# TALLER2.net
KiCad netlist of a schematic drawn in EAGLE
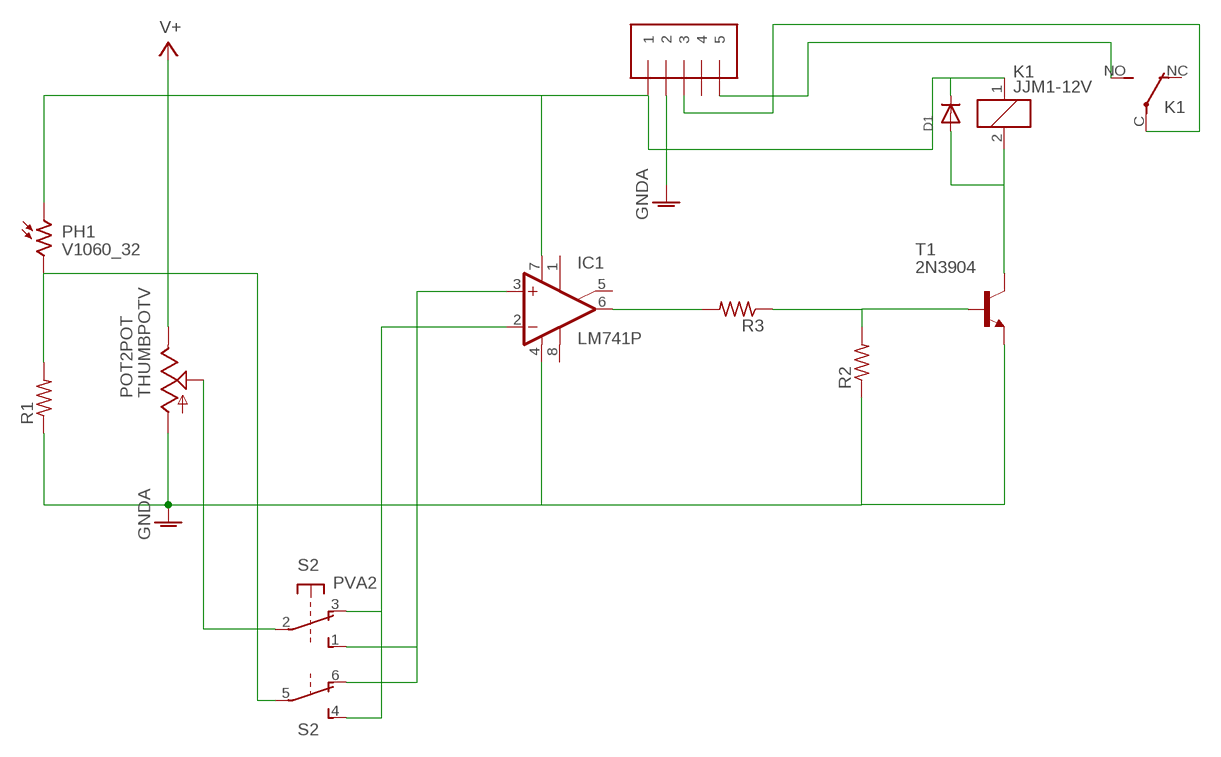
[diagram p0: schematic, sheet 1]

(export (version "E")
  (design (tool "Eeschema 10.0.6"))
  (components
    (comp (ref "D1")
      (value "DIODEDO-1N4148")
      (footprint "eagle-import:DO-1N4148")
      (libsource (lib "eagle-import") (part "DIODEDO-1N4148"))
    )
    (comp (ref "IC1")
      (value "LM741P")
      (footprint "eagle-import:DIL08")
      (libsource (lib "eagle-import") (part "741PLM"))
    )
    (comp (ref "J2")
      (value "1X5")
      (footprint "eagle-import:1X05-3.5MM")
      (libsource (lib "eagle-import") (part "1X5"))
    )
    (comp (ref "K1")
      (value "JJM1-12V")
      (footprint "eagle-import:JJM1C")
      (fields (field (name "MF") "AROMAT/ MATSUSHITA"))
      (libsource (lib "eagle-import") (part "JJM1-12V"))
    )
    (comp (ref "PH1")
      (value "V1060_32")
      (footprint "eagle-import:TO-5_V10")
      (libsource (lib "eagle-import") (part "?1060V_32"))
    )
    (comp (ref "POT2")
      (value "THUMBPOTV")
      (footprint "eagle-import:THUMBWHEELV")
      (libsource (lib "eagle-import") (part "THUMBPOTV"))
    )
    (comp (ref "R1")
      (value "R-US_0207/10")
      (footprint "eagle-import:0207_10")
      (libsource (lib "eagle-import") (part "R-US_0207/10"))
    )
    (comp (ref "R2")
      (value "R-US_0207/10")
      (footprint "eagle-import:0207_10")
      (libsource (lib "eagle-import") (part "R-US_0207/10"))
    )
    (comp (ref "R3")
      (value "R-US_0207/10")
      (footprint "eagle-import:0207_10")
      (libsource (lib "eagle-import") (part "R-US_0207/10"))
    )
    (comp (ref "S2")
      (value "PVA2")
      (footprint "eagle-import:PVA2F")
      (libsource (lib "eagle-import") (part "PVA2"))
    )
    (comp (ref "T1")
      (value "2N3904")
      (footprint "eagle-import:TO92")
      (libsource (lib "eagle-import") (part "2N3904"))
    )
  )
  (nets
    (net (code "1") (name "GNDA") (class "Default")
      (node (ref "IC1") (pin "4") (pinfunction "V-_4") (pintype "power_in"))
      (node (ref "J2") (pin "2") (pinfunction "2_2") (pintype "passive"))
      (node (ref "POT2") (pin "A") (pinfunction "A_A") (pintype "passive"))
      (node (ref "R1") (pin "1") (pinfunction "1_1") (pintype "passive"))
      (node (ref "R2") (pin "1") (pinfunction "1_1") (pintype "passive"))
      (node (ref "T1") (pin "3") (pinfunction "E_3") (pintype "passive"))
    )
    (net (code "2") (name "Net-(IC1-+IN)") (class "Default")
      (node (ref "IC1") (pin "3") (pinfunction "+IN_3") (pintype "input"))
      (node (ref "S2") (pin "1") (pinfunction "S_1") (pintype "passive"))
      (node (ref "S2") (pin "6") (pinfunction "O_6") (pintype "passive"))
    )
    (net (code "3") (name "Net-(IC1--IN)") (class "Default")
      (node (ref "IC1") (pin "2") (pinfunction "-IN_2") (pintype "input"))
      (node (ref "S2") (pin "3") (pinfunction "O_3") (pintype "passive"))
      (node (ref "S2") (pin "4") (pinfunction "S_4") (pintype "passive"))
    )
    (net (code "4") (name "Net-(IC1-OUT)") (class "Default")
      (node (ref "IC1") (pin "6") (pinfunction "OUT_6") (pintype "output"))
      (node (ref "R3") (pin "2") (pinfunction "2_2") (pintype "passive"))
    )
    (net (code "5") (name "Net-(K1B-P)") (class "Default")
      (node (ref "J2") (pin "3") (pinfunction "3_3") (pintype "passive"))
      (node (ref "K1") (pin "C") (pinfunction "P_C") (pintype "passive"))
    )
    (net (code "6") (name "Net-(K1B-S)") (class "Default")
      (node (ref "J2") (pin "5") (pinfunction "5_5") (pintype "passive"))
      (node (ref "K1") (pin "NO") (pinfunction "S_NO") (pintype "passive"))
    )
    (net (code "7") (name "Net-(S2A-P)") (class "Default")
      (node (ref "POT2") (pin "S") (pinfunction "S_S") (pintype "passive"))
      (node (ref "S2") (pin "2") (pinfunction "P_2") (pintype "passive"))
    )
    (net (code "8") (name "Net-(S2B-P)") (class "Default")
      (node (ref "PH1") (pin "2") (pinfunction "2_2") (pintype "passive"))
      (node (ref "R1") (pin "2") (pinfunction "2_2") (pintype "passive"))
      (node (ref "S2") (pin "5") (pinfunction "P_5") (pintype "passive"))
    )
    (net (code "9") (name "Net-(T1-B)") (class "Default")
      (node (ref "R2") (pin "2") (pinfunction "2_2") (pintype "passive"))
      (node (ref "R3") (pin "1") (pinfunction "1_1") (pintype "passive"))
      (node (ref "T1") (pin "2") (pinfunction "B_2") (pintype "passive"))
    )
    (net (code "10") (name "Net-(T1-C)") (class "Default")
      (node (ref "D1") (pin "A") (pinfunction "A_A") (pintype "passive"))
      (node (ref "K1") (pin "2") (pinfunction "2_2") (pintype "passive"))
      (node (ref "T1") (pin "1") (pinfunction "C_1") (pintype "passive"))
    )
    (net (code "11") (name "V+") (class "Default")
      (node (ref "D1") (pin "C") (pinfunction "C_C") (pintype "passive"))
      (node (ref "IC1") (pin "7") (pinfunction "V+_7") (pintype "power_in"))
      (node (ref "J2") (pin "1") (pinfunction "1_1") (pintype "passive"))
      (node (ref "K1") (pin "1") (pinfunction "1_1") (pintype "passive"))
      (node (ref "PH1") (pin "1") (pinfunction "1_1") (pintype "passive"))
      (node (ref "POT2") (pin "E") (pinfunction "E_E") (pintype "passive"))
    )
    (net (code "12") (name "unconnected-(IC1-ON1-Pad1)") (class "Default")
      (node (ref "IC1") (pin "1") (pinfunction "ON1_1") (pintype "passive"))
    )
    (net (code "13") (name "unconnected-(IC1-ON2-Pad5)") (class "Default")
      (node (ref "IC1") (pin "5") (pinfunction "ON2_5") (pintype "passive"))
    )
    (net (code "14") (name "unconnected-(IC1-OPT-Pad8)") (class "Default")
      (node (ref "IC1") (pin "8") (pinfunction "OPT_8") (pintype "passive"))
    )
    (net (code "15") (name "unconnected-(J2-Pad4)") (class "Default")
      (node (ref "J2") (pin "4") (pinfunction "4_4") (pintype "passive"))
    )
    (net (code "16") (name "unconnected-(K1B-O-PadNC)") (class "Default")
      (node (ref "K1") (pin "NC") (pinfunction "O_NC") (pintype "passive"))
    )
  )
)
